# main-unit-psu.net
KiCad netlist of a schematic drawn in EAGLE
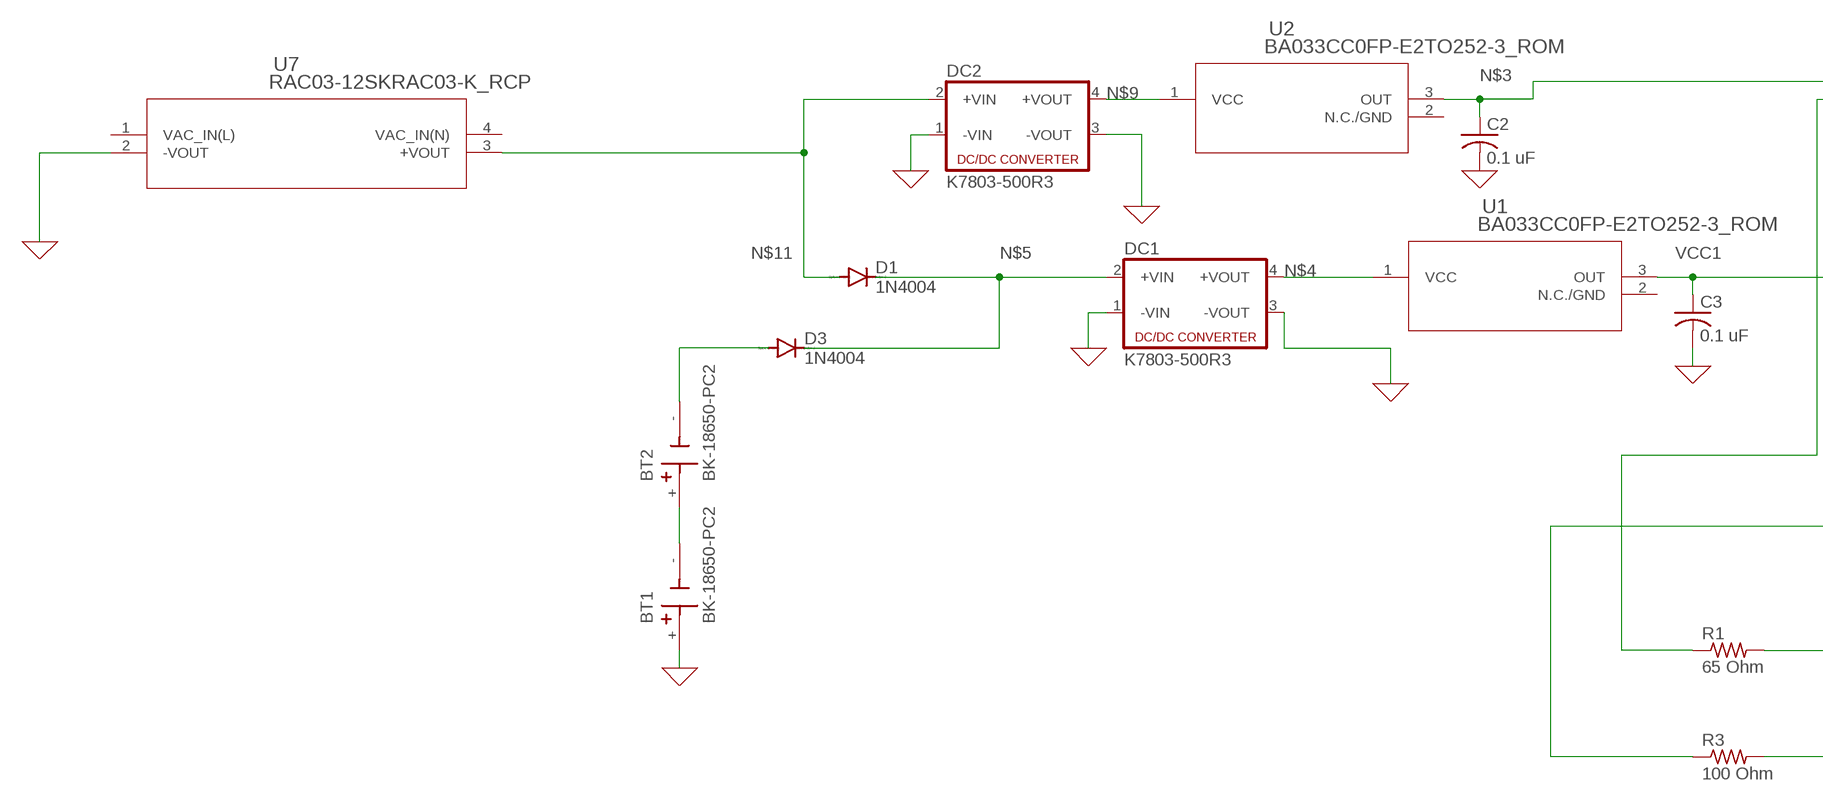
[diagram p0: schematic, sheet 1, part 1 of 2]
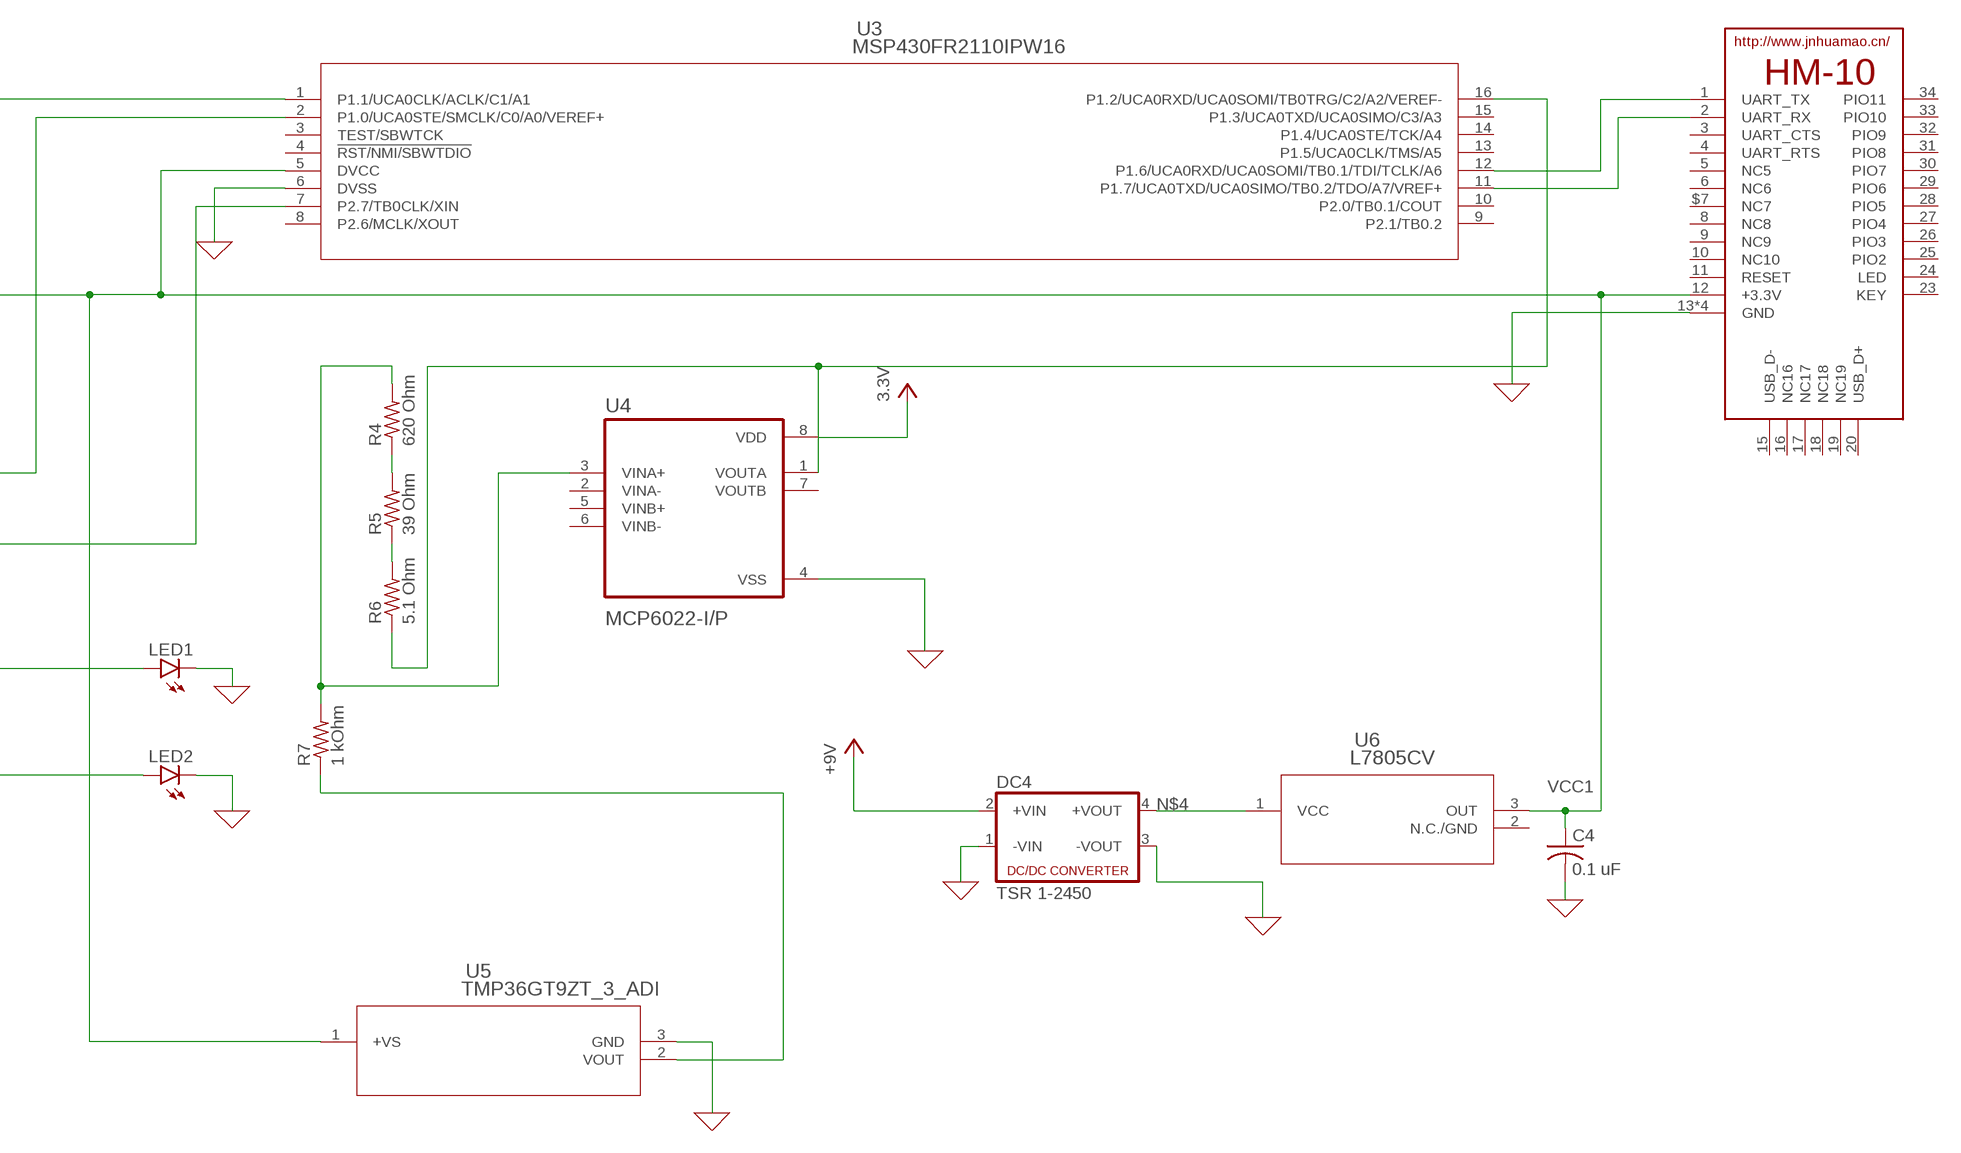
[diagram p1: schematic, sheet 1, part 2 of 2]

(export (version "E")
  (design (tool "Eeschema 10.0.6"))
  (components
    (comp (ref "BT1")
      (value "BK-18650-PC2")
      (footprint "eagle-import:BAT_BK-18650-PC2")
      (fields (field (name "MF") "MPD (Memory Protection Devices)"))
      (libsource (lib "eagle-import") (part "BK-18650-PC2"))
    )
    (comp (ref "BT2")
      (value "BK-18650-PC2")
      (footprint "eagle-import:BAT_BK-18650-PC2")
      (fields (field (name "MF") "MPD (Memory Protection Devices)"))
      (libsource (lib "eagle-import") (part "BK-18650-PC2"))
    )
    (comp (ref "C2")
      (value "0.1 uF")
      (footprint "eagle-import:C050-024X044")
      (libsource (lib "eagle-import") (part "C-US050-024X044"))
    )
    (comp (ref "C3")
      (value "0.1 uF")
      (footprint "eagle-import:C050-024X044")
      (libsource (lib "eagle-import") (part "C-US050-024X044"))
    )
    (comp (ref "C4")
      (value "0.1 uF")
      (footprint "eagle-import:C050-024X044")
      (libsource (lib "eagle-import") (part "C-US050-024X044"))
    )
    (comp (ref "D1")
      (value "1N4004")
      (footprint "eagle-import:DO41-10")
      (libsource (lib "eagle-import") (part "1N4004"))
    )
    (comp (ref "D3")
      (value "1N4004")
      (footprint "eagle-import:DO41-10")
      (libsource (lib "eagle-import") (part "1N4004"))
    )
    (comp (ref "DC1")
      (value "K7803-500R3")
      (footprint "eagle-import:NME")
      (fields (field (name "MF") "C & D TECHNOLOGIES, INC") (field (name "MPN") "NME1205D"))
      (libsource (lib "eagle-import") (part "NME"))
    )
    (comp (ref "DC2")
      (value "K7803-500R3")
      (footprint "eagle-import:NME")
      (fields (field (name "MF") "C & D TECHNOLOGIES, INC") (field (name "MPN") "NME1205D"))
      (libsource (lib "eagle-import") (part "NME"))
    )
    (comp (ref "DC4")
      (value "TSR 1-2450")
      (footprint "eagle-import:NME")
      (fields (field (name "MF") "C & D TECHNOLOGIES, INC") (field (name "MPN") "NME1205D"))
      (libsource (lib "eagle-import") (part "NME"))
    )
    (comp (ref "E1")
      (value "HM-10-BOARD")
      (footprint "eagle-import:26.9X13X2.2_BOARD")
      (fields (field (name "MF") "Jinan Huamao Technology") (field (name "MP") "HM-10"))
      (libsource (lib "eagle-import") (part "HM-10-BOARD"))
    )
    (comp (ref "LED1")
      (value "LED5MM")
      (footprint "eagle-import:LED5MM")
      (libsource (lib "eagle-import") (part "LED5MM"))
    )
    (comp (ref "LED2")
      (value "LED5MM")
      (footprint "eagle-import:LED5MM")
      (libsource (lib "eagle-import") (part "LED5MM"))
    )
    (comp (ref "R1")
      (value "65 Ohm")
      (footprint "eagle-import:0204_7")
      (libsource (lib "eagle-import") (part "R-US_0204/7"))
    )
    (comp (ref "R3")
      (value "100 Ohm")
      (footprint "eagle-import:0204_7")
      (libsource (lib "eagle-import") (part "R-US_0204/7"))
    )
    (comp (ref "R4")
      (value "620 Ohm")
      (footprint "eagle-import:0204_7")
      (libsource (lib "eagle-import") (part "R-US_0204/7"))
    )
    (comp (ref "R5")
      (value "39 Ohm")
      (footprint "eagle-import:0204_7")
      (libsource (lib "eagle-import") (part "R-US_0204/7"))
    )
    (comp (ref "R6")
      (value "5.1 Ohm")
      (footprint "eagle-import:0204_7")
      (libsource (lib "eagle-import") (part "R-US_0204/7"))
    )
    (comp (ref "R7")
      (value "1 kOhm")
      (footprint "eagle-import:0204_7")
      (libsource (lib "eagle-import") (part "R-US_0204/7"))
    )
    (comp (ref "U1")
      (value "BA033CC0FP-E2TO252-3_ROM")
      (footprint "eagle-import:TO252-3_ROM")
      (fields
        (field (name "MANUFACTURER_PART_NUMBER") "BA033CC0FP-E2")
        (field (name "COPYRIGHT") "Copyright (C) 2023 Ultra Librarian. All rights reserved.")
      )
      (libsource (lib "eagle-import") (part "BA033CC0FP-E2TO252-3_ROM"))
    )
    (comp (ref "U2")
      (value "BA033CC0FP-E2TO252-3_ROM")
      (footprint "eagle-import:TO252-3_ROM")
      (fields
        (field (name "MANUFACTURER_PART_NUMBER") "BA033CC0FP-E2")
        (field (name "COPYRIGHT") "Copyright (C) 2023 Ultra Librarian. All rights reserved.")
      )
      (libsource (lib "eagle-import") (part "BA033CC0FP-E2TO252-3_ROM"))
    )
    (comp (ref "U3")
      (value "MSP430FR2110IPW16")
      (footprint "eagle-import:PW16_TEX")
      (fields (field (name "COPYRIGHT") "Copyright (C) 2023 Ultra Librarian. All rights reserved."))
      (libsource (lib "eagle-import") (part "MSP430FR2110IPW16"))
    )
    (comp (ref "U4")
      (value "MCP6022-I/P")
      (footprint "eagle-import:DIP787W46P254L927H533Q8")
      (libsource (lib "eagle-import") (part "MCP6022-I/P"))
    )
    (comp (ref "U5")
      (value "TMP36GT9ZT_3_ADI")
      (footprint "eagle-import:T_3_ADI")
      (fields
        (field (name "MANUFACTURER_PART_NUMBER") "TMP36GT9Z")
        (field (name "COPYRIGHT") "Copyright (C) 2023 Ultra Librarian. All rights reserved.")
      )
      (libsource (lib "eagle-import") (part "TMP36GT9ZT_3_ADI"))
    )
    (comp (ref "U6")
      (value "L7805CV")
      (footprint "eagle-import:TO252-3_ROM")
      (fields
        (field (name "MANUFACTURER_PART_NUMBER") "BA033CC0FP-E2")
        (field (name "COPYRIGHT") "Copyright (C) 2023 Ultra Librarian. All rights reserved.")
      )
      (libsource (lib "eagle-import") (part "BA033CC0FP-E2TO252-3_ROM"))
    )
    (comp (ref "U7")
      (value "RAC03-12SKRAC03-K_RCP")
      (footprint "eagle-import:RAC03-K_RCP")
      (fields
        (field (name "MANUFACTURER_PART_NUMBER") "RAC03-12SK")
        (field (name "COPYRIGHT") "Copyright (C) 2023 Ultra Librarian. All rights reserved.")
      )
      (libsource (lib "eagle-import") (part "RAC03-12SKRAC03-K_RCP"))
    )
  )
  (nets
    (net (code "1") (name "+9V") (class "Default")
      (node (ref "DC4") (pin "2") (pinfunction "+VIN_2") (pintype "passive"))
    )
    (net (code "2") (name "/N$3") (class "Default")
      (node (ref "C2") (pin "1") (pinfunction "1_1") (pintype "passive"))
      (node (ref "U2") (pin "3") (pinfunction "OUT_3") (pintype "output"))
      (node (ref "U3") (pin "1") (pinfunction "P1.1/UCA0CLK/ACLK/C1/A1_1") (pintype "bidirectional"))
    )
    (net (code "3") (name "/N$4") (class "Default")
      (node (ref "DC1") (pin "4") (pinfunction "+VOUT_4") (pintype "passive"))
      (node (ref "DC4") (pin "4") (pinfunction "+VOUT_4") (pintype "passive"))
      (node (ref "U1") (pin "1") (pinfunction "VCC_1") (pintype "power_in"))
      (node (ref "U6") (pin "1") (pinfunction "VCC_1") (pintype "power_in"))
    )
    (net (code "4") (name "/N$5") (class "Default")
      (node (ref "D1") (pin "C") (pinfunction "C_C") (pintype "passive"))
      (node (ref "D3") (pin "C") (pinfunction "C_C") (pintype "passive"))
      (node (ref "DC1") (pin "2") (pinfunction "+VIN_2") (pintype "passive"))
    )
    (net (code "5") (name "/N$9") (class "Default")
      (node (ref "DC2") (pin "4") (pinfunction "+VOUT_4") (pintype "passive"))
      (node (ref "U2") (pin "1") (pinfunction "VCC_1") (pintype "power_in"))
    )
    (net (code "6") (name "/N$11") (class "Default")
      (node (ref "D1") (pin "A") (pinfunction "A_A") (pintype "passive"))
      (node (ref "DC2") (pin "2") (pinfunction "+VIN_2") (pintype "passive"))
      (node (ref "U7") (pin "3") (pinfunction "+VOUT_3") (pintype "output"))
    )
    (net (code "7") (name "/VAC_IN(L)") (class "Default")
      (node (ref "U7") (pin "1") (pinfunction "VAC_IN(L)_1") (pintype "power_in"))
    )
    (net (code "8") (name "/VAC_IN(N)") (class "Default")
      (node (ref "U7") (pin "4") (pinfunction "VAC_IN(N)_4") (pintype "power_in"))
    )
    (net (code "9") (name "/VCC1") (class "Default")
      (node (ref "C3") (pin "1") (pinfunction "1_1") (pintype "passive"))
      (node (ref "C4") (pin "1") (pinfunction "1_1") (pintype "passive"))
      (node (ref "E1") (pin "12") (pinfunction "+3.3V_12") (pintype "bidirectional"))
      (node (ref "U1") (pin "3") (pinfunction "OUT_3") (pintype "output"))
      (node (ref "U3") (pin "5") (pinfunction "DVCC_5") (pintype "power_in"))
      (node (ref "U5") (pin "1") (pinfunction "+VS_1") (pintype "power_in"))
      (node (ref "U6") (pin "3") (pinfunction "OUT_3") (pintype "output"))
    )
    (net (code "10") (name "3.3V") (class "Default")
      (node (ref "U4") (pin "8") (pinfunction "VDD_8") (pintype "power_in"))
    )
    (net (code "11") (name "GND") (class "Default")
      (node (ref "BT1") (pin "+") (pinfunction "+_+") (pintype "passive"))
      (node (ref "C2") (pin "2") (pinfunction "2_2") (pintype "passive"))
      (node (ref "C3") (pin "2") (pinfunction "2_2") (pintype "passive"))
      (node (ref "C4") (pin "2") (pinfunction "2_2") (pintype "passive"))
      (node (ref "DC1") (pin "1") (pinfunction "-VIN_1") (pintype "passive"))
      (node (ref "DC1") (pin "3") (pinfunction "-VOUT_3") (pintype "passive"))
      (node (ref "DC2") (pin "1") (pinfunction "-VIN_1") (pintype "passive"))
      (node (ref "DC2") (pin "3") (pinfunction "-VOUT_3") (pintype "passive"))
      (node (ref "DC4") (pin "1") (pinfunction "-VIN_1") (pintype "passive"))
      (node (ref "DC4") (pin "3") (pinfunction "-VOUT_3") (pintype "passive"))
      (node (ref "E1") (pin "13") (pinfunction "GND_13") (pintype "bidirectional"))
      (node (ref "E1") (pin "14") (pinfunction "GND_14") (pintype "bidirectional"))
      (node (ref "E1") (pin "21") (pinfunction "GND_21") (pintype "bidirectional"))
      (node (ref "E1") (pin "22") (pinfunction "GND_22") (pintype "bidirectional"))
      (node (ref "LED1") (pin "K") (pinfunction "C_K") (pintype "passive"))
      (node (ref "LED2") (pin "K") (pinfunction "C_K") (pintype "passive"))
      (node (ref "U3") (pin "6") (pinfunction "DVSS_6") (pintype "passive"))
      (node (ref "U4") (pin "4") (pinfunction "VSS_4") (pintype "power_in"))
      (node (ref "U5") (pin "3") (pinfunction "GND_3") (pintype "passive"))
      (node (ref "U7") (pin "2") (pinfunction "-VOUT_2") (pintype "output"))
    )
    (net (code "12") (name "Net-(BT1-Pad-)") (class "Default")
      (node (ref "BT1") (pin "-") (pinfunction "-_-") (pintype "passive"))
      (node (ref "BT2") (pin "+") (pinfunction "+_+") (pintype "passive"))
    )
    (net (code "13") (name "Net-(BT2-Pad-)") (class "Default")
      (node (ref "BT2") (pin "-") (pinfunction "-_-") (pintype "passive"))
      (node (ref "D3") (pin "A") (pinfunction "A_A") (pintype "passive"))
    )
    (net (code "14") (name "Net-(E1-UART_RX)") (class "Default")
      (node (ref "E1") (pin "2") (pinfunction "UART_RX_2") (pintype "bidirectional"))
      (node (ref "U3") (pin "11") (pinfunction "P1.7/UCA0TXD/UCA0SIMO/TB0.2/TDO/A7/VREF+_11") (pintype "bidirectional"))
    )
    (net (code "15") (name "Net-(E1-UART_TX)") (class "Default")
      (node (ref "E1") (pin "1") (pinfunction "UART_TX_1") (pintype "bidirectional"))
      (node (ref "U3") (pin "12") (pinfunction "P1.6/UCA0RXD/UCA0SOMI/TB0.1/TDI/TCLK/A6_12") (pintype "bidirectional"))
    )
    (net (code "16") (name "Net-(LED1-PadA)") (class "Default")
      (node (ref "LED1") (pin "A") (pinfunction "A_A") (pintype "passive"))
      (node (ref "R1") (pin "2") (pinfunction "2_2") (pintype "passive"))
    )
    (net (code "17") (name "Net-(LED2-PadA)") (class "Default")
      (node (ref "LED2") (pin "A") (pinfunction "A_A") (pintype "passive"))
      (node (ref "R3") (pin "2") (pinfunction "2_2") (pintype "passive"))
    )
    (net (code "18") (name "Net-(R4-Pad1)") (class "Default")
      (node (ref "R4") (pin "1") (pinfunction "1_1") (pintype "passive"))
      (node (ref "R5") (pin "2") (pinfunction "2_2") (pintype "passive"))
    )
    (net (code "19") (name "Net-(R5-Pad1)") (class "Default")
      (node (ref "R5") (pin "1") (pinfunction "1_1") (pintype "passive"))
      (node (ref "R6") (pin "2") (pinfunction "2_2") (pintype "passive"))
    )
    (net (code "20") (name "Net-(U3-P1.0{slash}UCA0STE{slash}SMCLK{slash}C0{slash}A0{slash}VEREF+)") (class "Default")
      (node (ref "R1") (pin "1") (pinfunction "1_1") (pintype "passive"))
      (node (ref "U3") (pin "2") (pinfunction "P1.0/UCA0STE/SMCLK/C0/A0/VEREF+_2") (pintype "bidirectional"))
    )
    (net (code "21") (name "Net-(U3-P1.2{slash}UCA0RXD{slash}UCA0SOMI{slash}TB0TRG{slash}C2{slash}A2{slash}VEREF-)") (class "Default")
      (node (ref "R6") (pin "1") (pinfunction "1_1") (pintype "passive"))
      (node (ref "U3") (pin "16") (pinfunction "P1.2/UCA0RXD/UCA0SOMI/TB0TRG/C2/A2/VEREF-_16") (pintype "bidirectional"))
      (node (ref "U4") (pin "1") (pinfunction "VOUTA_1") (pintype "output"))
    )
    (net (code "22") (name "Net-(U3-P2.7{slash}TB0CLK{slash}XIN)") (class "Default")
      (node (ref "R3") (pin "1") (pinfunction "1_1") (pintype "passive"))
      (node (ref "U3") (pin "7") (pinfunction "P2.7/TB0CLK/XIN_7") (pintype "bidirectional"))
    )
    (net (code "23") (name "Net-(U4-VINA+)") (class "Default")
      (node (ref "R4") (pin "2") (pinfunction "2_2") (pintype "passive"))
      (node (ref "R7") (pin "2") (pinfunction "2_2") (pintype "passive"))
      (node (ref "U4") (pin "3") (pinfunction "VINA+_3") (pintype "input"))
    )
    (net (code "24") (name "Net-(U5-VOUT)") (class "Default")
      (node (ref "R7") (pin "1") (pinfunction "1_1") (pintype "passive"))
      (node (ref "U5") (pin "2") (pinfunction "VOUT_2") (pintype "passive"))
    )
    (net (code "25") (name "unconnected-(E1-KEY-Pad23)") (class "Default")
      (node (ref "E1") (pin "23") (pinfunction "KEY_23") (pintype "bidirectional"))
    )
    (net (code "26") (name "unconnected-(E1-LED-Pad24)") (class "Default")
      (node (ref "E1") (pin "24") (pinfunction "LED_24") (pintype "bidirectional"))
    )
    (net (code "27") (name "unconnected-(E1-NC5-Pad5)") (class "Default")
      (node (ref "E1") (pin "5") (pinfunction "NC5_5") (pintype "bidirectional"))
    )
    (net (code "28") (name "unconnected-(E1-NC6-Pad6)") (class "Default")
      (node (ref "E1") (pin "6") (pinfunction "NC6_6") (pintype "bidirectional"))
    )
    (net (code "29") (name "unconnected-(E1-NC7-Pad$7)") (class "Default")
      (node (ref "E1") (pin "$7") (pinfunction "NC7_$7") (pintype "bidirectional"))
    )
    (net (code "30") (name "unconnected-(E1-NC8-Pad8)") (class "Default")
      (node (ref "E1") (pin "8") (pinfunction "NC8_8") (pintype "bidirectional"))
    )
    (net (code "31") (name "unconnected-(E1-NC9-Pad9)") (class "Default")
      (node (ref "E1") (pin "9") (pinfunction "NC9_9") (pintype "bidirectional"))
    )
    (net (code "32") (name "unconnected-(E1-NC10-Pad10)") (class "Default")
      (node (ref "E1") (pin "10") (pinfunction "NC10_10") (pintype "bidirectional"))
    )
    (net (code "33") (name "unconnected-(E1-NC16-Pad16)") (class "Default")
      (node (ref "E1") (pin "16") (pinfunction "NC16_16") (pintype "bidirectional"))
    )
    (net (code "34") (name "unconnected-(E1-NC17-Pad17)") (class "Default")
      (node (ref "E1") (pin "17") (pinfunction "NC17_17") (pintype "bidirectional"))
    )
    (net (code "35") (name "unconnected-(E1-NC18-Pad18)") (class "Default")
      (node (ref "E1") (pin "18") (pinfunction "NC18_18") (pintype "bidirectional"))
    )
    (net (code "36") (name "unconnected-(E1-NC19-Pad19)") (class "Default")
      (node (ref "E1") (pin "19") (pinfunction "NC19_19") (pintype "bidirectional"))
    )
    (net (code "37") (name "unconnected-(E1-PIO2-Pad25)") (class "Default")
      (node (ref "E1") (pin "25") (pinfunction "PIO2_25") (pintype "bidirectional"))
    )
    (net (code "38") (name "unconnected-(E1-PIO3-Pad26)") (class "Default")
      (node (ref "E1") (pin "26") (pinfunction "PIO3_26") (pintype "bidirectional"))
    )
    (net (code "39") (name "unconnected-(E1-PIO4-Pad27)") (class "Default")
      (node (ref "E1") (pin "27") (pinfunction "PIO4_27") (pintype "bidirectional"))
    )
    (net (code "40") (name "unconnected-(E1-PIO5-Pad28)") (class "Default")
      (node (ref "E1") (pin "28") (pinfunction "PIO5_28") (pintype "bidirectional"))
    )
    (net (code "41") (name "unconnected-(E1-PIO6-Pad29)") (class "Default")
      (node (ref "E1") (pin "29") (pinfunction "PIO6_29") (pintype "bidirectional"))
    )
    (net (code "42") (name "unconnected-(E1-PIO7-Pad30)") (class "Default")
      (node (ref "E1") (pin "30") (pinfunction "PIO7_30") (pintype "bidirectional"))
    )
    (net (code "43") (name "unconnected-(E1-PIO8-Pad31)") (class "Default")
      (node (ref "E1") (pin "31") (pinfunction "PIO8_31") (pintype "bidirectional"))
    )
    (net (code "44") (name "unconnected-(E1-PIO9-Pad32)") (class "Default")
      (node (ref "E1") (pin "32") (pinfunction "PIO9_32") (pintype "bidirectional"))
    )
    (net (code "45") (name "unconnected-(E1-PIO10-Pad33)") (class "Default")
      (node (ref "E1") (pin "33") (pinfunction "PIO10_33") (pintype "bidirectional"))
    )
    (net (code "46") (name "unconnected-(E1-PIO11-Pad34)") (class "Default")
      (node (ref "E1") (pin "34") (pinfunction "PIO11_34") (pintype "bidirectional"))
    )
    (net (code "47") (name "unconnected-(E1-RESET-Pad11)") (class "Default")
      (node (ref "E1") (pin "11") (pinfunction "RESET_11") (pintype "bidirectional"))
    )
    (net (code "48") (name "unconnected-(E1-UART_CTS-Pad3)") (class "Default")
      (node (ref "E1") (pin "3") (pinfunction "UART_CTS_3") (pintype "bidirectional"))
    )
    (net (code "49") (name "unconnected-(E1-UART_RTS-Pad4)") (class "Default")
      (node (ref "E1") (pin "4") (pinfunction "UART_RTS_4") (pintype "bidirectional"))
    )
    (net (code "50") (name "unconnected-(E1-USB_D+-Pad20)") (class "Default")
      (node (ref "E1") (pin "20") (pinfunction "USB_D+_20") (pintype "bidirectional"))
    )
    (net (code "51") (name "unconnected-(E1-USB_D--Pad15)") (class "Default")
      (node (ref "E1") (pin "15") (pinfunction "USB_D-_15") (pintype "bidirectional"))
    )
    (net (code "52") (name "unconnected-(U1-N.C.{slash}GND-Pad2)") (class "Default")
      (node (ref "U1") (pin "2") (pinfunction "N.C./GND_2") (pintype "no_connect"))
    )
    (net (code "53") (name "unconnected-(U2-N.C.{slash}GND-Pad2)") (class "Default")
      (node (ref "U2") (pin "2") (pinfunction "N.C./GND_2") (pintype "no_connect"))
    )
    (net (code "54") (name "unconnected-(U3-P1.3{slash}UCA0TXD{slash}UCA0SIMO{slash}C3{slash}A3-Pad15)") (class "Default")
      (node (ref "U3") (pin "15") (pinfunction "P1.3/UCA0TXD/UCA0SIMO/C3/A3_15") (pintype "bidirectional"))
    )
    (net (code "55") (name "unconnected-(U3-P1.4{slash}UCA0STE{slash}TCK{slash}A4-Pad14)") (class "Default")
      (node (ref "U3") (pin "14") (pinfunction "P1.4/UCA0STE/TCK/A4_14") (pintype "bidirectional"))
    )
    (net (code "56") (name "unconnected-(U3-P1.5{slash}UCA0CLK{slash}TMS{slash}A5-Pad13)") (class "Default")
      (node (ref "U3") (pin "13") (pinfunction "P1.5/UCA0CLK/TMS/A5_13") (pintype "bidirectional"))
    )
    (net (code "57") (name "unconnected-(U3-P2.0{slash}TB0.1{slash}COUT-Pad10)") (class "Default")
      (node (ref "U3") (pin "10") (pinfunction "P2.0/TB0.1/COUT_10") (pintype "bidirectional"))
    )
    (net (code "58") (name "unconnected-(U3-P2.1{slash}TB0.2-Pad9)") (class "Default")
      (node (ref "U3") (pin "9") (pinfunction "P2.1/TB0.2_9") (pintype "bidirectional"))
    )
    (net (code "59") (name "unconnected-(U3-P2.6{slash}MCLK{slash}XOUT-Pad8)") (class "Default")
      (node (ref "U3") (pin "8") (pinfunction "P2.6/MCLK/XOUT_8") (pintype "bidirectional"))
    )
    (net (code "60") (name "unconnected-(U3-TEST{slash}SBWTCK-Pad3)") (class "Default")
      (node (ref "U3") (pin "3") (pinfunction "TEST/SBWTCK_3") (pintype "input"))
    )
    (net (code "61") (name "unconnected-(U3-~{RST{slash}NMI{slash}SBWTDIO}-Pad4)") (class "Default")
      (node (ref "U3") (pin "4") (pinfunction "~{RST/NMI/SBWTDIO}_4") (pintype "bidirectional"))
    )
    (net (code "62") (name "unconnected-(U4-VINA--Pad2)") (class "Default")
      (node (ref "U4") (pin "2") (pinfunction "VINA-_2") (pintype "input"))
    )
    (net (code "63") (name "unconnected-(U4-VINB+-Pad5)") (class "Default")
      (node (ref "U4") (pin "5") (pinfunction "VINB+_5") (pintype "input"))
    )
    (net (code "64") (name "unconnected-(U4-VINB--Pad6)") (class "Default")
      (node (ref "U4") (pin "6") (pinfunction "VINB-_6") (pintype "input"))
    )
    (net (code "65") (name "unconnected-(U4-VOUTB-Pad7)") (class "Default")
      (node (ref "U4") (pin "7") (pinfunction "VOUTB_7") (pintype "output"))
    )
    (net (code "66") (name "unconnected-(U6-N.C.{slash}GND-Pad2)") (class "Default")
      (node (ref "U6") (pin "2") (pinfunction "N.C./GND_2") (pintype "no_connect"))
    )
  )
)
